# quantik.net
KiCad netlist of a schematic drawn in EAGLE
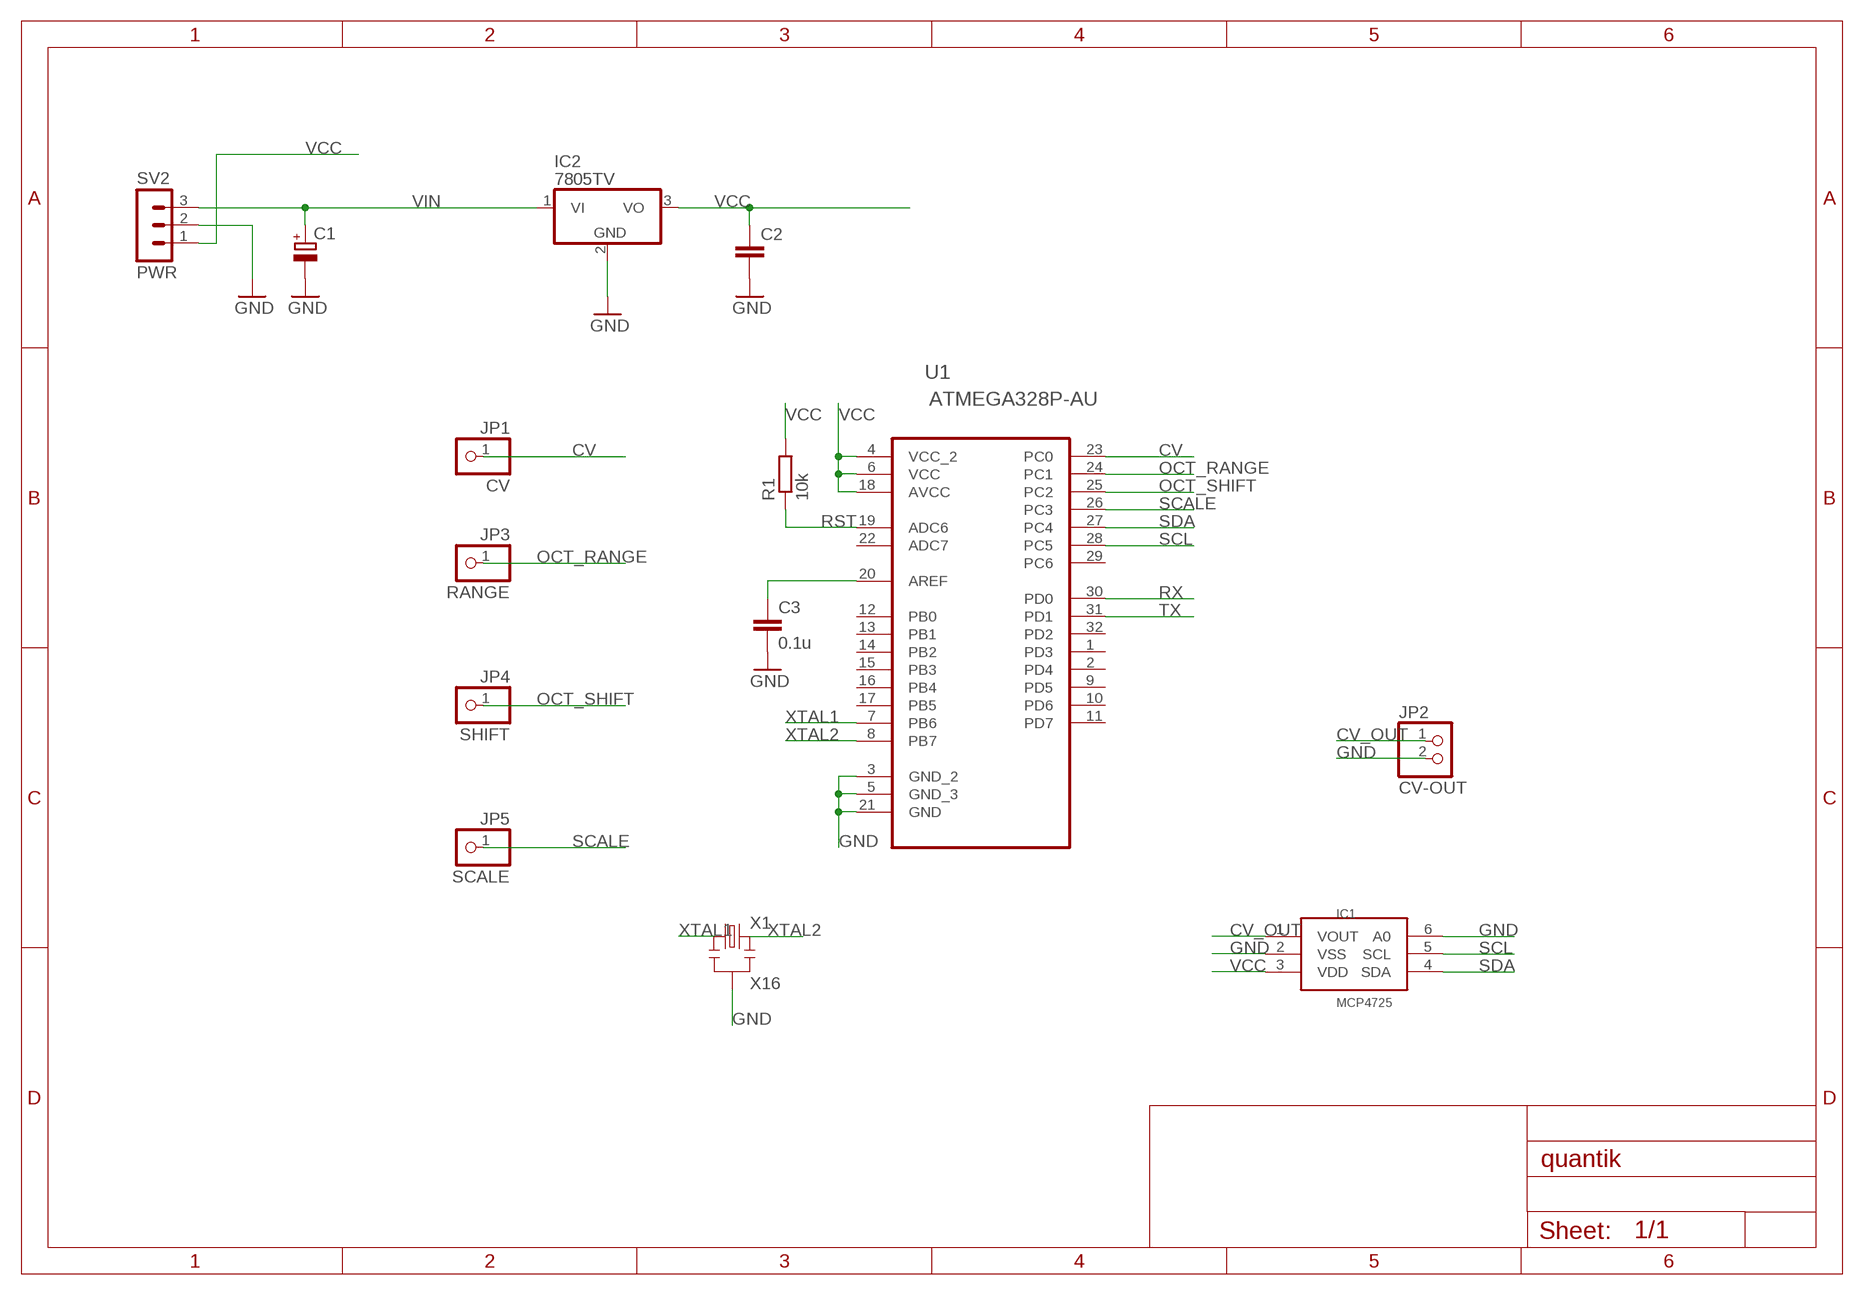
[diagram p0: schematic, sheet 1]

(export (version "E")
  (design (tool "Eeschema 10.0.6"))
  (components
    (comp (ref "C1")
      (value "CPOL-EUE5-10.5")
      (footprint "eagle-import:E5-10,5")
      (libsource (lib "eagle-import") (part "CPOL-EUE5-10.5"))
    )
    (comp (ref "C2")
      (value "C-EU050-030X075")
      (footprint "eagle-import:C050-030X075")
      (libsource (lib "eagle-import") (part "C-EU050-030X075"))
    )
    (comp (ref "C3")
      (value "0.1u")
      (footprint "eagle-import:C0805")
      (libsource (lib "eagle-import") (part "C-EUC0805"))
    )
    (comp (ref "IC1")
      (value "MCP4725")
      (footprint "eagle-import:SOT23-6")
      (libsource (lib "eagle-import") (part "MCP4725"))
    )
    (comp (ref "IC2")
      (value "7805TV")
      (footprint "eagle-import:TO220V")
      (libsource (lib "eagle-import") (part "78TV05"))
    )
    (comp (ref "JP1")
      (value "CV")
      (footprint "eagle-import:1X01")
      (libsource (lib "eagle-import") (part "PINHD-1X1"))
    )
    (comp (ref "JP2")
      (value "CV-OUT")
      (footprint "eagle-import:1X02")
      (libsource (lib "eagle-import") (part "PINHD-1X2"))
    )
    (comp (ref "JP3")
      (value "RANGE")
      (footprint "eagle-import:1X01")
      (libsource (lib "eagle-import") (part "PINHD-1X1"))
    )
    (comp (ref "JP4")
      (value "SHIFT")
      (footprint "eagle-import:1X01")
      (libsource (lib "eagle-import") (part "PINHD-1X1"))
    )
    (comp (ref "JP5")
      (value "SCALE")
      (footprint "eagle-import:1X01")
      (libsource (lib "eagle-import") (part "PINHD-1X1"))
    )
    (comp (ref "R1")
      (value "10k")
      (footprint "eagle-import:R0805")
      (libsource (lib "eagle-import") (part "R-EU_R0805"))
    )
    (comp (ref "SV2")
      (value "PWR")
      (footprint "eagle-import:MA03-1")
      (libsource (lib "eagle-import") (part "MA03-1"))
    )
    (comp (ref "U1")
      (value "ATMEGA328P-AU")
      (footprint "eagle-import:QFP80P900X900X120-32N")
      (libsource (lib "eagle-import") (part "ATMEGA328P-AU"))
    )
    (comp (ref "X1")
      (value "X16")
      (footprint "eagle-import:RESONATOR_SMD")
      (libsource (lib "eagle-import") (part "RESONATOR_16MHZ"))
    )
  )
  (nets
    (net (code "1") (name "/CV") (class "Default")
      (node (ref "JP1") (pin "1") (pinfunction "1_1") (pintype "passive"))
      (node (ref "U1") (pin "23") (pinfunction "PC0_23") (pintype "bidirectional"))
    )
    (net (code "2") (name "/CV_OUT") (class "Default")
      (node (ref "IC1") (pin "1") (pinfunction "VOUT_1") (pintype "bidirectional"))
      (node (ref "JP2") (pin "1") (pinfunction "1_1") (pintype "passive"))
    )
    (net (code "3") (name "/OCT_RANGE") (class "Default")
      (node (ref "JP3") (pin "1") (pinfunction "1_1") (pintype "passive"))
      (node (ref "U1") (pin "24") (pinfunction "PC1_24") (pintype "bidirectional"))
    )
    (net (code "4") (name "/OCT_SHIFT") (class "Default")
      (node (ref "JP4") (pin "1") (pinfunction "1_1") (pintype "passive"))
      (node (ref "U1") (pin "25") (pinfunction "PC2_25") (pintype "bidirectional"))
    )
    (net (code "5") (name "/RST") (class "Default")
      (node (ref "R1") (pin "1") (pinfunction "1_1") (pintype "passive"))
      (node (ref "U1") (pin "19") (pinfunction "ADC6_19") (pintype "input"))
    )
    (net (code "6") (name "/RX") (class "Default")
      (node (ref "U1") (pin "30") (pinfunction "PD0_30") (pintype "bidirectional"))
    )
    (net (code "7") (name "/SCALE") (class "Default")
      (node (ref "JP5") (pin "1") (pinfunction "1_1") (pintype "passive"))
      (node (ref "U1") (pin "26") (pinfunction "PC3_26") (pintype "bidirectional"))
    )
    (net (code "8") (name "/SCL") (class "Default")
      (node (ref "IC1") (pin "5") (pinfunction "SCL_5") (pintype "bidirectional"))
      (node (ref "U1") (pin "28") (pinfunction "PC5_28") (pintype "bidirectional"))
    )
    (net (code "9") (name "/SDA") (class "Default")
      (node (ref "IC1") (pin "4") (pinfunction "SDA_4") (pintype "bidirectional"))
      (node (ref "U1") (pin "27") (pinfunction "PC4_27") (pintype "bidirectional"))
    )
    (net (code "10") (name "/TX") (class "Default")
      (node (ref "U1") (pin "31") (pinfunction "PD1_31") (pintype "bidirectional"))
    )
    (net (code "11") (name "/VCC") (class "Default")
      (node (ref "C2") (pin "1") (pinfunction "1_1") (pintype "passive"))
      (node (ref "IC1") (pin "3") (pinfunction "VDD_3") (pintype "bidirectional"))
      (node (ref "IC2") (pin "3") (pinfunction "VO_3") (pintype "passive"))
      (node (ref "R1") (pin "2") (pinfunction "2_2") (pintype "passive"))
      (node (ref "SV2") (pin "1") (pinfunction "1_1") (pintype "passive"))
      (node (ref "U1") (pin "18") (pinfunction "AVCC_18") (pintype "power_in"))
      (node (ref "U1") (pin "4") (pinfunction "VCC_2_4") (pintype "power_in"))
      (node (ref "U1") (pin "6") (pinfunction "VCC_6") (pintype "power_in"))
    )
    (net (code "12") (name "/VIN") (class "Default")
      (node (ref "C1") (pin "+") (pinfunction "+_+") (pintype "passive"))
      (node (ref "IC2") (pin "1") (pinfunction "VI_1") (pintype "input"))
      (node (ref "SV2") (pin "3") (pinfunction "3_3") (pintype "passive"))
    )
    (net (code "13") (name "/XTAL1") (class "Default")
      (node (ref "U1") (pin "7") (pinfunction "PB6_7") (pintype "bidirectional"))
      (node (ref "X1") (pin "1") (pinfunction "1_1") (pintype "passive"))
    )
    (net (code "14") (name "/XTAL2") (class "Default")
      (node (ref "U1") (pin "8") (pinfunction "PB7_8") (pintype "bidirectional"))
      (node (ref "X1") (pin "3") (pinfunction "3_3") (pintype "passive"))
    )
    (net (code "15") (name "GND") (class "Default")
      (node (ref "C1") (pin "-") (pinfunction "-_-") (pintype "passive"))
      (node (ref "C2") (pin "2") (pinfunction "2_2") (pintype "passive"))
      (node (ref "C3") (pin "2") (pinfunction "2_2") (pintype "passive"))
      (node (ref "IC1") (pin "2") (pinfunction "VSS_2") (pintype "bidirectional"))
      (node (ref "IC1") (pin "6") (pinfunction "A0_6") (pintype "bidirectional"))
      (node (ref "IC2") (pin "2") (pinfunction "GND_2") (pintype "passive"))
      (node (ref "JP2") (pin "2") (pinfunction "2_2") (pintype "passive"))
      (node (ref "SV2") (pin "2") (pinfunction "2_2") (pintype "passive"))
      (node (ref "U1") (pin "21") (pinfunction "GND_21") (pintype "passive"))
      (node (ref "U1") (pin "3") (pinfunction "GND_2_3") (pintype "passive"))
      (node (ref "U1") (pin "5") (pinfunction "GND_3_5") (pintype "passive"))
      (node (ref "X1") (pin "2") (pinfunction "2_2") (pintype "passive"))
    )
    (net (code "16") (name "Net-(U1-AREF)") (class "Default")
      (node (ref "C3") (pin "1") (pinfunction "1_1") (pintype "passive"))
      (node (ref "U1") (pin "20") (pinfunction "AREF_20") (pintype "input"))
    )
    (net (code "17") (name "unconnected-(U1-ADC7-Pad22)") (class "Default")
      (node (ref "U1") (pin "22") (pinfunction "ADC7_22") (pintype "input"))
    )
    (net (code "18") (name "unconnected-(U1-PB0-Pad12)") (class "Default")
      (node (ref "U1") (pin "12") (pinfunction "PB0_12") (pintype "bidirectional"))
    )
    (net (code "19") (name "unconnected-(U1-PB1-Pad13)") (class "Default")
      (node (ref "U1") (pin "13") (pinfunction "PB1_13") (pintype "bidirectional"))
    )
    (net (code "20") (name "unconnected-(U1-PB2-Pad14)") (class "Default")
      (node (ref "U1") (pin "14") (pinfunction "PB2_14") (pintype "bidirectional"))
    )
    (net (code "21") (name "unconnected-(U1-PB3-Pad15)") (class "Default")
      (node (ref "U1") (pin "15") (pinfunction "PB3_15") (pintype "bidirectional"))
    )
    (net (code "22") (name "unconnected-(U1-PB4-Pad16)") (class "Default")
      (node (ref "U1") (pin "16") (pinfunction "PB4_16") (pintype "bidirectional"))
    )
    (net (code "23") (name "unconnected-(U1-PB5-Pad17)") (class "Default")
      (node (ref "U1") (pin "17") (pinfunction "PB5_17") (pintype "bidirectional"))
    )
    (net (code "24") (name "unconnected-(U1-PC6-Pad29)") (class "Default")
      (node (ref "U1") (pin "29") (pinfunction "PC6_29") (pintype "bidirectional"))
    )
    (net (code "25") (name "unconnected-(U1-PD2-Pad32)") (class "Default")
      (node (ref "U1") (pin "32") (pinfunction "PD2_32") (pintype "bidirectional"))
    )
    (net (code "26") (name "unconnected-(U1-PD3-Pad1)") (class "Default")
      (node (ref "U1") (pin "1") (pinfunction "PD3_1") (pintype "bidirectional"))
    )
    (net (code "27") (name "unconnected-(U1-PD4-Pad2)") (class "Default")
      (node (ref "U1") (pin "2") (pinfunction "PD4_2") (pintype "bidirectional"))
    )
    (net (code "28") (name "unconnected-(U1-PD5-Pad9)") (class "Default")
      (node (ref "U1") (pin "9") (pinfunction "PD5_9") (pintype "bidirectional"))
    )
    (net (code "29") (name "unconnected-(U1-PD6-Pad10)") (class "Default")
      (node (ref "U1") (pin "10") (pinfunction "PD6_10") (pintype "bidirectional"))
    )
    (net (code "30") (name "unconnected-(U1-PD7-Pad11)") (class "Default")
      (node (ref "U1") (pin "11") (pinfunction "PD7_11") (pintype "bidirectional"))
    )
  )
)
